# LCD.net
KiCad netlist of a schematic drawn in Altium Designer
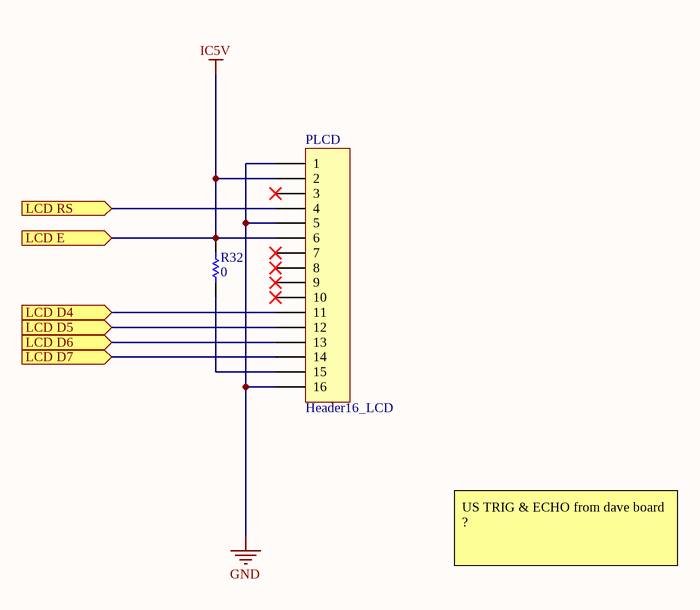
[diagram p0: LCD.SchDoc]

(export (version "E")
  (design (tool "Eeschema 10.0.6"))
  (components
    (comp (ref "PLCD")
      (value "Header16_LCD")
      (footprint "HDR1X16_LCD")
      (description "Header, 16-Pin Female")
      (fields (field (name "MPN") "PPPC161LFBN-RC"))
      (libsource (lib "esd_library") (part "Header16_LCD"))
    )
    (comp (ref "R32")
      (value "0")
      (description "Resistor")
      (libsource (lib "Simulation Generic Components") (part "Resistor"))
    )
  )
  (nets
    (net (code "1") (name "/LCD D4") (class "Default")
      (node (ref "PLCD") (pin "11") (pinfunction "11_11") (pintype "passive"))
    )
    (net (code "2") (name "/LCD D5") (class "Default")
      (node (ref "PLCD") (pin "12") (pinfunction "12_12") (pintype "passive"))
    )
    (net (code "3") (name "/LCD D6") (class "Default")
      (node (ref "PLCD") (pin "13") (pinfunction "13_13") (pintype "passive"))
    )
    (net (code "4") (name "/LCD D7") (class "Default")
      (node (ref "PLCD") (pin "14") (pinfunction "14_14") (pintype "passive"))
    )
    (net (code "5") (name "/LCD RS") (class "Default")
      (node (ref "PLCD") (pin "4") (pinfunction "4_4") (pintype "passive"))
    )
    (net (code "6") (name "GND") (class "Default")
      (node (ref "PLCD") (pin "1") (pinfunction "1_1") (pintype "passive"))
      (node (ref "PLCD") (pin "16") (pinfunction "16_16") (pintype "passive"))
      (node (ref "PLCD") (pin "5") (pinfunction "5_5") (pintype "passive"))
    )
    (net (code "7") (name "IC5V") (class "Default")
      (node (ref "PLCD") (pin "2") (pinfunction "2_2") (pintype "passive"))
      (node (ref "PLCD") (pin "6") (pinfunction "6_6") (pintype "passive"))
      (node (ref "R32") (pin "1") (pinfunction "1_1") (pintype "passive"))
    )
    (net (code "8") (name "Net-(PLCD-Pad15)") (class "Default")
      (node (ref "PLCD") (pin "15") (pinfunction "15_15") (pintype "passive"))
      (node (ref "R32") (pin "2") (pinfunction "2_2") (pintype "passive"))
    )
    (net (code "9") (name "unconnected-(PLCD-Pad3)") (class "Default")
      (node (ref "PLCD") (pin "3") (pinfunction "3_3") (pintype "passive+no_connect"))
    )
    (net (code "10") (name "unconnected-(PLCD-Pad7)") (class "Default")
      (node (ref "PLCD") (pin "7") (pinfunction "7_7") (pintype "passive+no_connect"))
    )
    (net (code "11") (name "unconnected-(PLCD-Pad8)") (class "Default")
      (node (ref "PLCD") (pin "8") (pinfunction "8_8") (pintype "passive+no_connect"))
    )
    (net (code "12") (name "unconnected-(PLCD-Pad9)") (class "Default")
      (node (ref "PLCD") (pin "9") (pinfunction "9_9") (pintype "passive+no_connect"))
    )
    (net (code "13") (name "unconnected-(PLCD-Pad10)") (class "Default")
      (node (ref "PLCD") (pin "10") (pinfunction "10_10") (pintype "passive+no_connect"))
    )
  )
)
